# PATA_Breakout.net
KiCad netlist of a schematic drawn in EAGLE
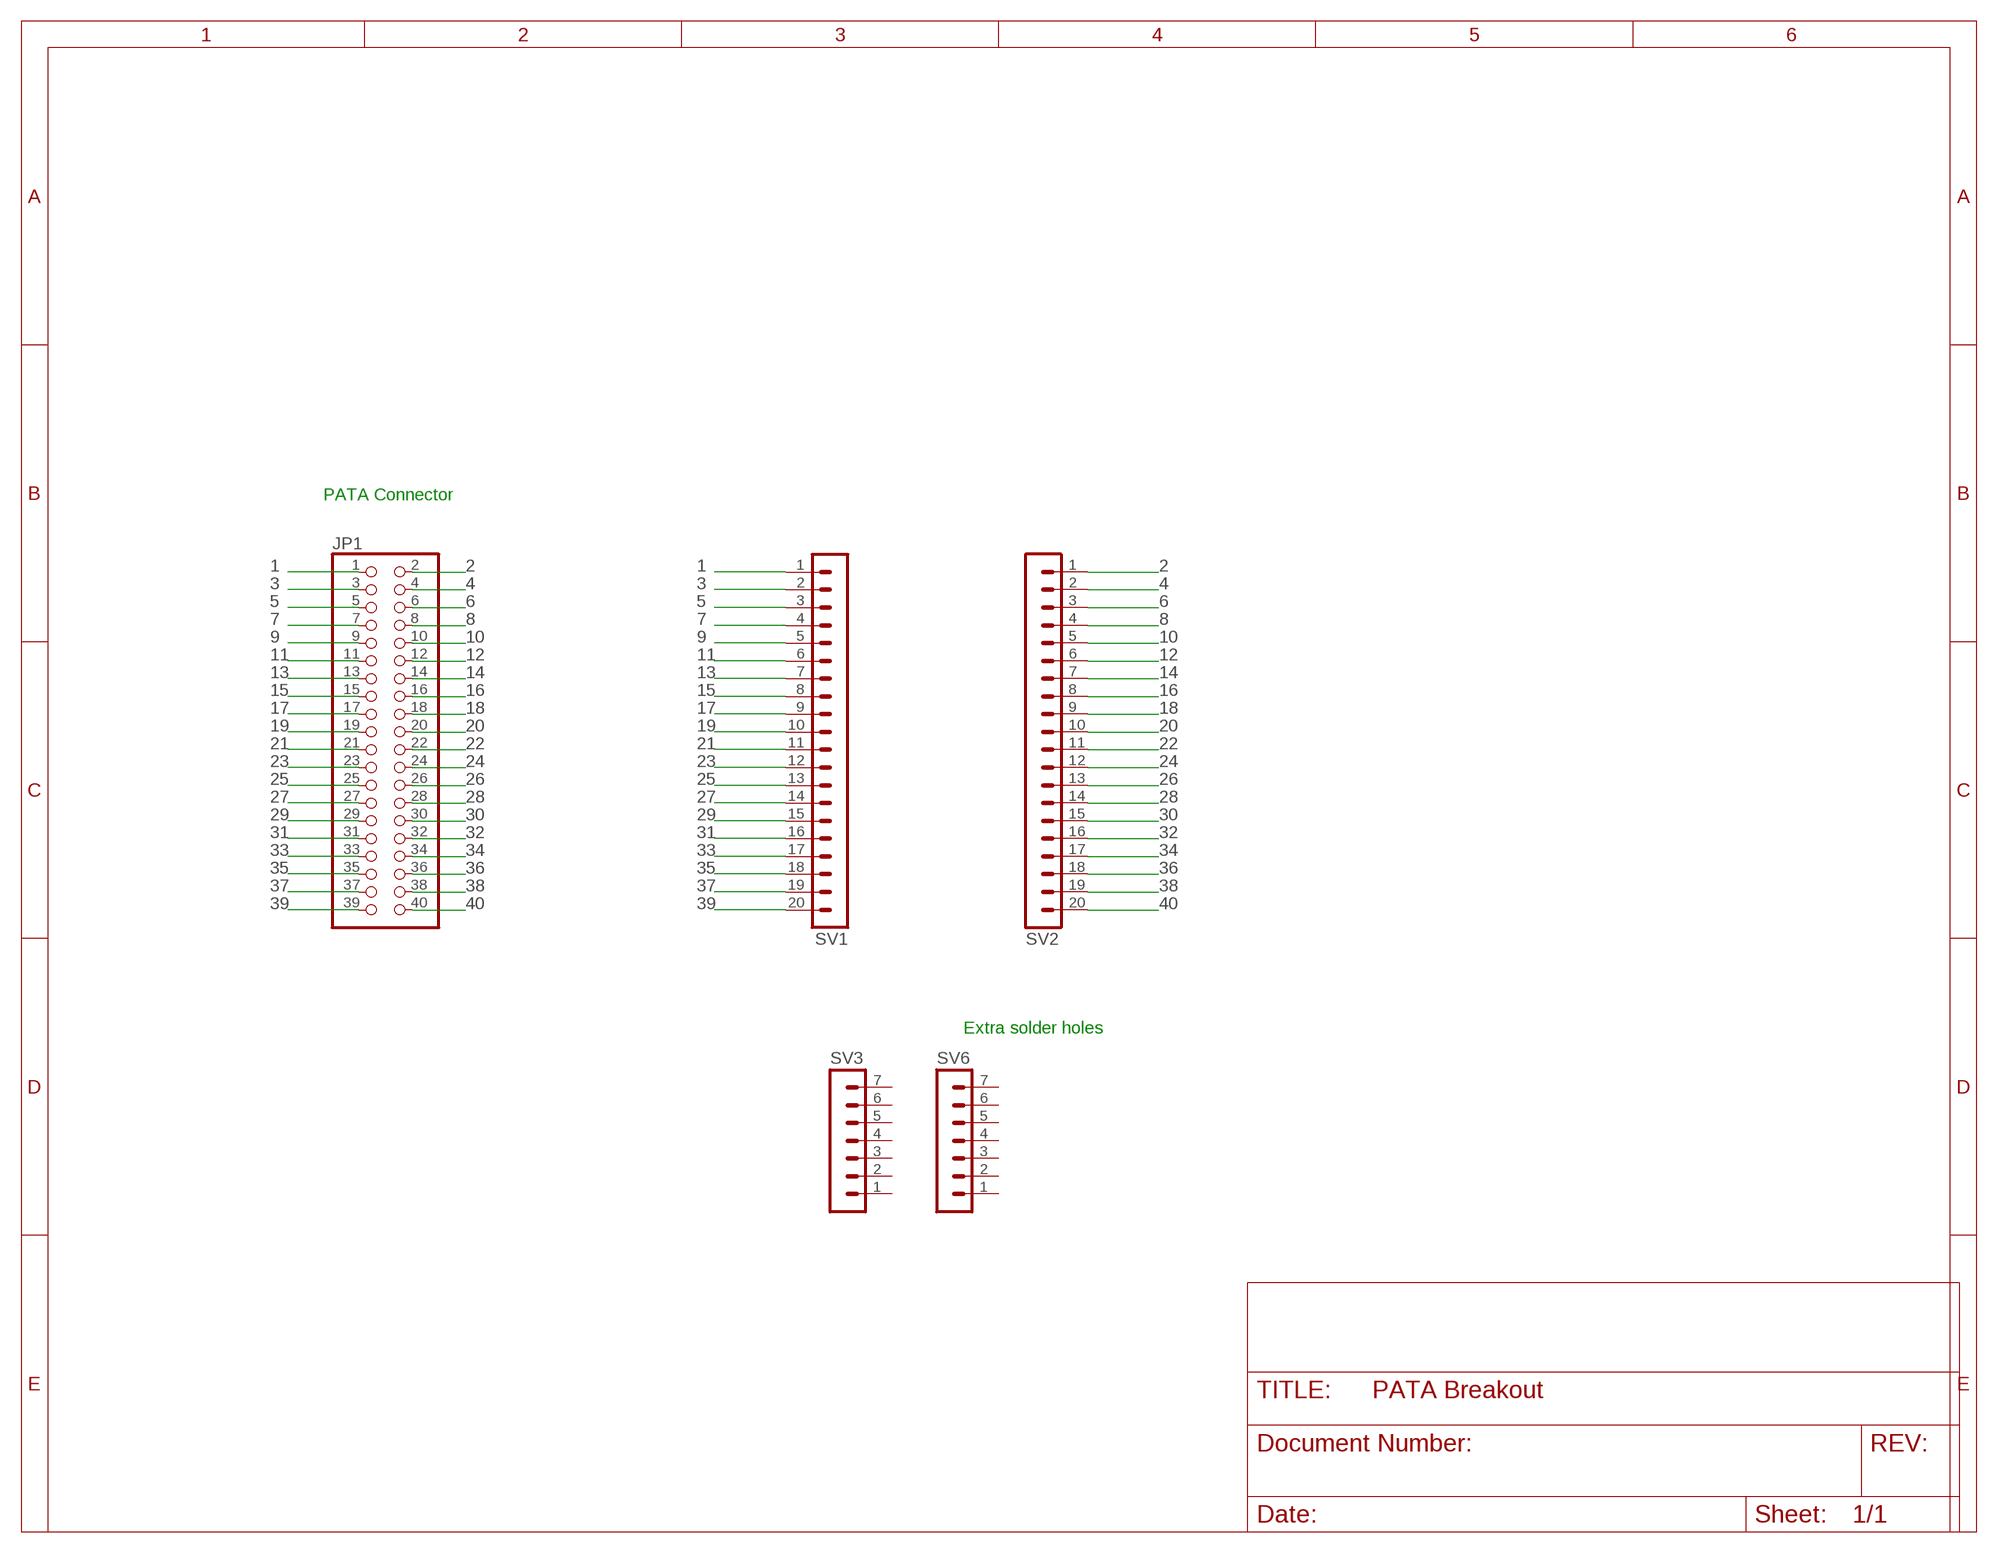
[diagram p0: schematic, sheet 1]

(export (version "E")
  (design (tool "Eeschema 10.0.6"))
  (components
    (comp (ref "JP1")
      (value "PINHD-2X20")
      (footprint "eagle-import:2X20")
      (libsource (lib "eagle-import") (part "PINHD-2X20"))
    )
    (comp (ref "SV1")
      (value "MA20-1L")
      (footprint "eagle-import:MA20-1L")
      (libsource (lib "eagle-import") (part "MA20-1L"))
    )
    (comp (ref "SV2")
      (value "MA20-1L")
      (footprint "eagle-import:MA20-1L")
      (libsource (lib "eagle-import") (part "MA20-1L"))
    )
    (comp (ref "SV3")
      (value "MA07-1")
      (footprint "eagle-import:MA07-1")
      (libsource (lib "eagle-import") (part "MA07-1"))
    )
    (comp (ref "SV6")
      (value "MA07-1")
      (footprint "eagle-import:MA07-1")
      (libsource (lib "eagle-import") (part "MA07-1"))
    )
  )
  (nets
    (net (code "1") (name "/1") (class "Default")
      (node (ref "JP1") (pin "1") (pinfunction "1_1") (pintype "passive"))
      (node (ref "SV1") (pin "1") (pinfunction "1_1") (pintype "passive"))
    )
    (net (code "2") (name "/2") (class "Default")
      (node (ref "JP1") (pin "2") (pinfunction "2_2") (pintype "passive"))
      (node (ref "SV2") (pin "1") (pinfunction "1_1") (pintype "passive"))
    )
    (net (code "3") (name "/3") (class "Default")
      (node (ref "JP1") (pin "3") (pinfunction "3_3") (pintype "passive"))
      (node (ref "SV1") (pin "2") (pinfunction "2_2") (pintype "passive"))
    )
    (net (code "4") (name "/4") (class "Default")
      (node (ref "JP1") (pin "4") (pinfunction "4_4") (pintype "passive"))
      (node (ref "SV2") (pin "2") (pinfunction "2_2") (pintype "passive"))
    )
    (net (code "5") (name "/5") (class "Default")
      (node (ref "JP1") (pin "5") (pinfunction "5_5") (pintype "passive"))
      (node (ref "SV1") (pin "3") (pinfunction "3_3") (pintype "passive"))
    )
    (net (code "6") (name "/6") (class "Default")
      (node (ref "JP1") (pin "6") (pinfunction "6_6") (pintype "passive"))
      (node (ref "SV2") (pin "3") (pinfunction "3_3") (pintype "passive"))
    )
    (net (code "7") (name "/7") (class "Default")
      (node (ref "JP1") (pin "7") (pinfunction "7_7") (pintype "passive"))
      (node (ref "SV1") (pin "4") (pinfunction "4_4") (pintype "passive"))
    )
    (net (code "8") (name "/8") (class "Default")
      (node (ref "JP1") (pin "8") (pinfunction "8_8") (pintype "passive"))
      (node (ref "SV2") (pin "4") (pinfunction "4_4") (pintype "passive"))
    )
    (net (code "9") (name "/9") (class "Default")
      (node (ref "JP1") (pin "9") (pinfunction "9_9") (pintype "passive"))
      (node (ref "SV1") (pin "5") (pinfunction "5_5") (pintype "passive"))
    )
    (net (code "10") (name "/10") (class "Default")
      (node (ref "JP1") (pin "10") (pinfunction "10_10") (pintype "passive"))
      (node (ref "SV2") (pin "5") (pinfunction "5_5") (pintype "passive"))
    )
    (net (code "11") (name "/11") (class "Default")
      (node (ref "JP1") (pin "11") (pinfunction "11_11") (pintype "passive"))
      (node (ref "SV1") (pin "6") (pinfunction "6_6") (pintype "passive"))
    )
    (net (code "12") (name "/12") (class "Default")
      (node (ref "JP1") (pin "12") (pinfunction "12_12") (pintype "passive"))
      (node (ref "SV2") (pin "6") (pinfunction "6_6") (pintype "passive"))
    )
    (net (code "13") (name "/13") (class "Default")
      (node (ref "JP1") (pin "13") (pinfunction "13_13") (pintype "passive"))
      (node (ref "SV1") (pin "7") (pinfunction "7_7") (pintype "passive"))
    )
    (net (code "14") (name "/14") (class "Default")
      (node (ref "JP1") (pin "14") (pinfunction "14_14") (pintype "passive"))
      (node (ref "SV2") (pin "7") (pinfunction "7_7") (pintype "passive"))
    )
    (net (code "15") (name "/15") (class "Default")
      (node (ref "JP1") (pin "15") (pinfunction "15_15") (pintype "passive"))
      (node (ref "SV1") (pin "8") (pinfunction "8_8") (pintype "passive"))
    )
    (net (code "16") (name "/16") (class "Default")
      (node (ref "JP1") (pin "16") (pinfunction "16_16") (pintype "passive"))
      (node (ref "SV2") (pin "8") (pinfunction "8_8") (pintype "passive"))
    )
    (net (code "17") (name "/17") (class "Default")
      (node (ref "JP1") (pin "17") (pinfunction "17_17") (pintype "passive"))
      (node (ref "SV1") (pin "9") (pinfunction "9_9") (pintype "passive"))
    )
    (net (code "18") (name "/18") (class "Default")
      (node (ref "JP1") (pin "18") (pinfunction "18_18") (pintype "passive"))
      (node (ref "SV2") (pin "9") (pinfunction "9_9") (pintype "passive"))
    )
    (net (code "19") (name "/19") (class "Default")
      (node (ref "JP1") (pin "19") (pinfunction "19_19") (pintype "passive"))
      (node (ref "SV1") (pin "10") (pinfunction "10_10") (pintype "passive"))
    )
    (net (code "20") (name "/20") (class "Default")
      (node (ref "JP1") (pin "20") (pinfunction "20_20") (pintype "passive"))
      (node (ref "SV2") (pin "10") (pinfunction "10_10") (pintype "passive"))
    )
    (net (code "21") (name "/21") (class "Default")
      (node (ref "JP1") (pin "21") (pinfunction "21_21") (pintype "passive"))
      (node (ref "SV1") (pin "11") (pinfunction "11_11") (pintype "passive"))
    )
    (net (code "22") (name "/22") (class "Default")
      (node (ref "JP1") (pin "22") (pinfunction "22_22") (pintype "passive"))
      (node (ref "SV2") (pin "11") (pinfunction "11_11") (pintype "passive"))
    )
    (net (code "23") (name "/23") (class "Default")
      (node (ref "JP1") (pin "23") (pinfunction "23_23") (pintype "passive"))
      (node (ref "SV1") (pin "12") (pinfunction "12_12") (pintype "passive"))
    )
    (net (code "24") (name "/24") (class "Default")
      (node (ref "JP1") (pin "24") (pinfunction "24_24") (pintype "passive"))
      (node (ref "SV2") (pin "12") (pinfunction "12_12") (pintype "passive"))
    )
    (net (code "25") (name "/25") (class "Default")
      (node (ref "JP1") (pin "25") (pinfunction "25_25") (pintype "passive"))
      (node (ref "SV1") (pin "13") (pinfunction "13_13") (pintype "passive"))
    )
    (net (code "26") (name "/26") (class "Default")
      (node (ref "JP1") (pin "26") (pinfunction "26_26") (pintype "passive"))
      (node (ref "SV2") (pin "13") (pinfunction "13_13") (pintype "passive"))
    )
    (net (code "27") (name "/27") (class "Default")
      (node (ref "JP1") (pin "27") (pinfunction "27_27") (pintype "passive"))
      (node (ref "SV1") (pin "14") (pinfunction "14_14") (pintype "passive"))
    )
    (net (code "28") (name "/28") (class "Default")
      (node (ref "JP1") (pin "28") (pinfunction "28_28") (pintype "passive"))
      (node (ref "SV2") (pin "14") (pinfunction "14_14") (pintype "passive"))
    )
    (net (code "29") (name "/29") (class "Default")
      (node (ref "JP1") (pin "29") (pinfunction "29_29") (pintype "passive"))
      (node (ref "SV1") (pin "15") (pinfunction "15_15") (pintype "passive"))
    )
    (net (code "30") (name "/30") (class "Default")
      (node (ref "JP1") (pin "30") (pinfunction "30_30") (pintype "passive"))
      (node (ref "SV2") (pin "15") (pinfunction "15_15") (pintype "passive"))
    )
    (net (code "31") (name "/31") (class "Default")
      (node (ref "JP1") (pin "31") (pinfunction "31_31") (pintype "passive"))
      (node (ref "SV1") (pin "16") (pinfunction "16_16") (pintype "passive"))
    )
    (net (code "32") (name "/32") (class "Default")
      (node (ref "JP1") (pin "32") (pinfunction "32_32") (pintype "passive"))
      (node (ref "SV2") (pin "16") (pinfunction "16_16") (pintype "passive"))
    )
    (net (code "33") (name "/33") (class "Default")
      (node (ref "JP1") (pin "33") (pinfunction "33_33") (pintype "passive"))
      (node (ref "SV1") (pin "17") (pinfunction "17_17") (pintype "passive"))
    )
    (net (code "34") (name "/34") (class "Default")
      (node (ref "JP1") (pin "34") (pinfunction "34_34") (pintype "passive"))
      (node (ref "SV2") (pin "17") (pinfunction "17_17") (pintype "passive"))
    )
    (net (code "35") (name "/35") (class "Default")
      (node (ref "JP1") (pin "35") (pinfunction "35_35") (pintype "passive"))
      (node (ref "SV1") (pin "18") (pinfunction "18_18") (pintype "passive"))
    )
    (net (code "36") (name "/36") (class "Default")
      (node (ref "JP1") (pin "36") (pinfunction "36_36") (pintype "passive"))
      (node (ref "SV2") (pin "18") (pinfunction "18_18") (pintype "passive"))
    )
    (net (code "37") (name "/37") (class "Default")
      (node (ref "JP1") (pin "37") (pinfunction "37_37") (pintype "passive"))
      (node (ref "SV1") (pin "19") (pinfunction "19_19") (pintype "passive"))
    )
    (net (code "38") (name "/38") (class "Default")
      (node (ref "JP1") (pin "38") (pinfunction "38_38") (pintype "passive"))
      (node (ref "SV2") (pin "19") (pinfunction "19_19") (pintype "passive"))
    )
    (net (code "39") (name "/39") (class "Default")
      (node (ref "JP1") (pin "39") (pinfunction "39_39") (pintype "passive"))
      (node (ref "SV1") (pin "20") (pinfunction "20_20") (pintype "passive"))
    )
    (net (code "40") (name "/40") (class "Default")
      (node (ref "JP1") (pin "40") (pinfunction "40_40") (pintype "passive"))
      (node (ref "SV2") (pin "20") (pinfunction "20_20") (pintype "passive"))
    )
    (net (code "41") (name "unconnected-(SV3-Pad1)") (class "Default")
      (node (ref "SV3") (pin "1") (pinfunction "1_1") (pintype "passive"))
    )
    (net (code "42") (name "unconnected-(SV3-Pad2)") (class "Default")
      (node (ref "SV3") (pin "2") (pinfunction "2_2") (pintype "passive"))
    )
    (net (code "43") (name "unconnected-(SV3-Pad3)") (class "Default")
      (node (ref "SV3") (pin "3") (pinfunction "3_3") (pintype "passive"))
    )
    (net (code "44") (name "unconnected-(SV3-Pad4)") (class "Default")
      (node (ref "SV3") (pin "4") (pinfunction "4_4") (pintype "passive"))
    )
    (net (code "45") (name "unconnected-(SV3-Pad5)") (class "Default")
      (node (ref "SV3") (pin "5") (pinfunction "5_5") (pintype "passive"))
    )
    (net (code "46") (name "unconnected-(SV3-Pad6)") (class "Default")
      (node (ref "SV3") (pin "6") (pinfunction "6_6") (pintype "passive"))
    )
    (net (code "47") (name "unconnected-(SV3-Pad7)") (class "Default")
      (node (ref "SV3") (pin "7") (pinfunction "7_7") (pintype "passive"))
    )
    (net (code "48") (name "unconnected-(SV6-Pad1)") (class "Default")
      (node (ref "SV6") (pin "1") (pinfunction "1_1") (pintype "passive"))
    )
    (net (code "49") (name "unconnected-(SV6-Pad2)") (class "Default")
      (node (ref "SV6") (pin "2") (pinfunction "2_2") (pintype "passive"))
    )
    (net (code "50") (name "unconnected-(SV6-Pad3)") (class "Default")
      (node (ref "SV6") (pin "3") (pinfunction "3_3") (pintype "passive"))
    )
    (net (code "51") (name "unconnected-(SV6-Pad4)") (class "Default")
      (node (ref "SV6") (pin "4") (pinfunction "4_4") (pintype "passive"))
    )
    (net (code "52") (name "unconnected-(SV6-Pad5)") (class "Default")
      (node (ref "SV6") (pin "5") (pinfunction "5_5") (pintype "passive"))
    )
    (net (code "53") (name "unconnected-(SV6-Pad6)") (class "Default")
      (node (ref "SV6") (pin "6") (pinfunction "6_6") (pintype "passive"))
    )
    (net (code "54") (name "unconnected-(SV6-Pad7)") (class "Default")
      (node (ref "SV6") (pin "7") (pinfunction "7_7") (pintype "passive"))
    )
  )
)
